# Input.net
KiCad netlist of a schematic drawn in Altium Designer
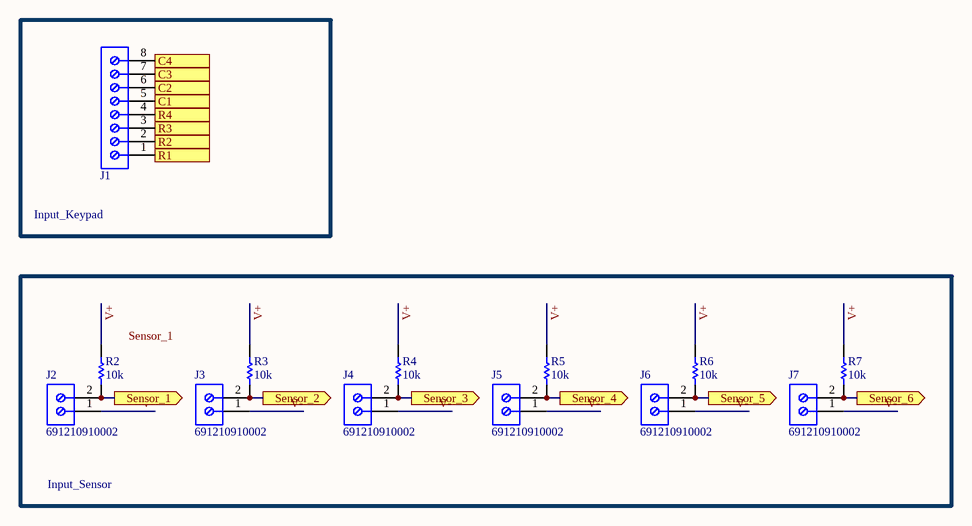
[diagram p0: Input.SchDoc]

(export (version "E")
  (design (tool "Eeschema 10.0.6"))
  (components
    (comp (ref "J1")
      (value "691210910008")
      (footprint "691210910008")
      (description "WR-TBL Series 2109 Horizontal Entry, Through Hole, pitch 2.54mm, 8p")
      (fields (field (name "MANUFACTURER") "Wurth Elektronik"))
      (libsource (lib "Altium_WR-TBL (rev22a)") (part "691210910008"))
    )
    (comp (ref "J2")
      (value "691210910002")
      (footprint "691210910002")
      (description "WR-TBL Serie 2109 Horizontal Entry, Rising Cage Clamp, pitch 2.54mm, 2p")
      (fields (field (name "PUBLISHER") "Wurth Elektronik"))
      (libsource (lib "691322310002.") (part "691210910002"))
    )
    (comp (ref "J3")
      (value "691210910002")
      (footprint "691210910002")
      (description "WR-TBL Serie 2109 Horizontal Entry, Rising Cage Clamp, pitch 2.54mm, 2p")
      (fields (field (name "PUBLISHER") "Wurth Elektronik"))
      (libsource (lib "691322310002.") (part "691210910002"))
    )
    (comp (ref "J4")
      (value "691210910002")
      (footprint "691210910002")
      (description "WR-TBL Serie 2109 Horizontal Entry, Rising Cage Clamp, pitch 2.54mm, 2p")
      (fields (field (name "PUBLISHER") "Wurth Elektronik"))
      (libsource (lib "691322310002.") (part "691210910002"))
    )
    (comp (ref "J5")
      (value "691210910002")
      (footprint "691210910002")
      (description "WR-TBL Serie 2109 Horizontal Entry, Rising Cage Clamp, pitch 2.54mm, 2p")
      (fields (field (name "PUBLISHER") "Wurth Elektronik"))
      (libsource (lib "691322310002.") (part "691210910002"))
    )
    (comp (ref "J6")
      (value "691210910002")
      (footprint "691210910002")
      (description "WR-TBL Serie 2109 Horizontal Entry, Rising Cage Clamp, pitch 2.54mm, 2p")
      (fields (field (name "PUBLISHER") "Wurth Elektronik"))
      (libsource (lib "691322310002.") (part "691210910002"))
    )
    (comp (ref "J7")
      (value "691210910002")
      (footprint "691210910002")
      (description "WR-TBL Serie 2109 Horizontal Entry, Rising Cage Clamp, pitch 2.54mm, 2p")
      (fields (field (name "PUBLISHER") "Wurth Elektronik"))
      (libsource (lib "691322310002.") (part "691210910002"))
    )
    (comp (ref "R2")
      (value "10k")
      (footprint "RES-SM-0603")
      (description "RES SMD 10K OHM 1% 1/4W 0603")
      (fields (field (name "MFR") "Rohm Semiconductor") (field (name "TOLERANCE") "±1%"))
      (libsource (lib "PIF_Library") (part "RESISTOR SMD"))
    )
    (comp (ref "R3")
      (value "10k")
      (footprint "RES-SM-0603")
      (description "RES SMD 10K OHM 1% 1/4W 0603")
      (fields (field (name "MFR") "Rohm Semiconductor") (field (name "TOLERANCE") "±1%"))
      (libsource (lib "PIF_Library") (part "RESISTOR SMD"))
    )
    (comp (ref "R4")
      (value "10k")
      (footprint "RES-SM-0603")
      (description "RES SMD 10K OHM 1% 1/4W 0603")
      (fields (field (name "MFR") "Rohm Semiconductor") (field (name "TOLERANCE") "±1%"))
      (libsource (lib "PIF_Library") (part "RESISTOR SMD"))
    )
    (comp (ref "R5")
      (value "10k")
      (footprint "RES-SM-0603")
      (description "RES SMD 10K OHM 1% 1/4W 0603")
      (fields (field (name "MFR") "Rohm Semiconductor") (field (name "TOLERANCE") "±1%"))
      (libsource (lib "PIF_Library") (part "RESISTOR SMD"))
    )
    (comp (ref "R6")
      (value "10k")
      (footprint "RES-SM-0603")
      (description "RES SMD 10K OHM 1% 1/4W 0603")
      (fields (field (name "MFR") "Rohm Semiconductor") (field (name "TOLERANCE") "±1%"))
      (libsource (lib "PIF_Library") (part "RESISTOR SMD"))
    )
    (comp (ref "R7")
      (value "10k")
      (footprint "RES-SM-0603")
      (description "RES SMD 10K OHM 1% 1/4W 0603")
      (fields (field (name "MFR") "Rohm Semiconductor") (field (name "TOLERANCE") "±1%"))
      (libsource (lib "PIF_Library") (part "RESISTOR SMD"))
    )
  )
  (nets
    (net (code "1") (name "/C1") (class "Default")
      (node (ref "J1") (pin "5") (pinfunction "5_5") (pintype "passive"))
    )
    (net (code "2") (name "/C2") (class "Default")
      (node (ref "J1") (pin "6") (pinfunction "6_6") (pintype "passive"))
    )
    (net (code "3") (name "/C3") (class "Default")
      (node (ref "J1") (pin "7") (pinfunction "7_7") (pintype "passive"))
    )
    (net (code "4") (name "/C4") (class "Default")
      (node (ref "J1") (pin "8") (pinfunction "8_8") (pintype "passive"))
    )
    (net (code "5") (name "/R1") (class "Default")
      (node (ref "J1") (pin "1") (pinfunction "1_1") (pintype "passive"))
    )
    (net (code "6") (name "/R2") (class "Default")
      (node (ref "J1") (pin "2") (pinfunction "2_2") (pintype "passive"))
    )
    (net (code "7") (name "/R3") (class "Default")
      (node (ref "J1") (pin "3") (pinfunction "3_3") (pintype "passive"))
    )
    (net (code "8") (name "/R4") (class "Default")
      (node (ref "J1") (pin "4") (pinfunction "4_4") (pintype "passive"))
    )
    (net (code "9") (name "/Sensor_1") (class "Default")
      (node (ref "J2") (pin "2") (pinfunction "2_2") (pintype "passive"))
      (node (ref "R2") (pin "1") (pinfunction "1_1") (pintype "passive"))
    )
    (net (code "10") (name "/Sensor_2") (class "Default")
      (node (ref "J3") (pin "2") (pinfunction "2_2") (pintype "passive"))
      (node (ref "R3") (pin "1") (pinfunction "1_1") (pintype "passive"))
    )
    (net (code "11") (name "/Sensor_3") (class "Default")
      (node (ref "J4") (pin "2") (pinfunction "2_2") (pintype "passive"))
      (node (ref "R4") (pin "1") (pinfunction "1_1") (pintype "passive"))
    )
    (net (code "12") (name "/Sensor_4") (class "Default")
      (node (ref "J5") (pin "2") (pinfunction "2_2") (pintype "passive"))
      (node (ref "R5") (pin "1") (pinfunction "1_1") (pintype "passive"))
    )
    (net (code "13") (name "/Sensor_5") (class "Default")
      (node (ref "J6") (pin "2") (pinfunction "2_2") (pintype "passive"))
      (node (ref "R6") (pin "1") (pinfunction "1_1") (pintype "passive"))
    )
    (net (code "14") (name "/Sensor_6") (class "Default")
      (node (ref "J7") (pin "2") (pinfunction "2_2") (pintype "passive"))
      (node (ref "R7") (pin "1") (pinfunction "1_1") (pintype "passive"))
    )
    (net (code "15") (name "/V+") (class "Default")
      (node (ref "R2") (pin "2") (pinfunction "2_2") (pintype "passive"))
      (node (ref "R3") (pin "2") (pinfunction "2_2") (pintype "passive"))
      (node (ref "R4") (pin "2") (pinfunction "2_2") (pintype "passive"))
      (node (ref "R5") (pin "2") (pinfunction "2_2") (pintype "passive"))
      (node (ref "R6") (pin "2") (pinfunction "2_2") (pintype "passive"))
      (node (ref "R7") (pin "2") (pinfunction "2_2") (pintype "passive"))
    )
    (net (code "16") (name "/V-") (class "Default")
      (node (ref "J2") (pin "1") (pinfunction "1_1") (pintype "passive"))
      (node (ref "J3") (pin "1") (pinfunction "1_1") (pintype "passive"))
      (node (ref "J4") (pin "1") (pinfunction "1_1") (pintype "passive"))
      (node (ref "J5") (pin "1") (pinfunction "1_1") (pintype "passive"))
      (node (ref "J6") (pin "1") (pinfunction "1_1") (pintype "passive"))
      (node (ref "J7") (pin "1") (pinfunction "1_1") (pintype "passive"))
    )
  )
)
